# 5V_Buck.net
KiCad netlist of a schematic drawn in Altium Designer
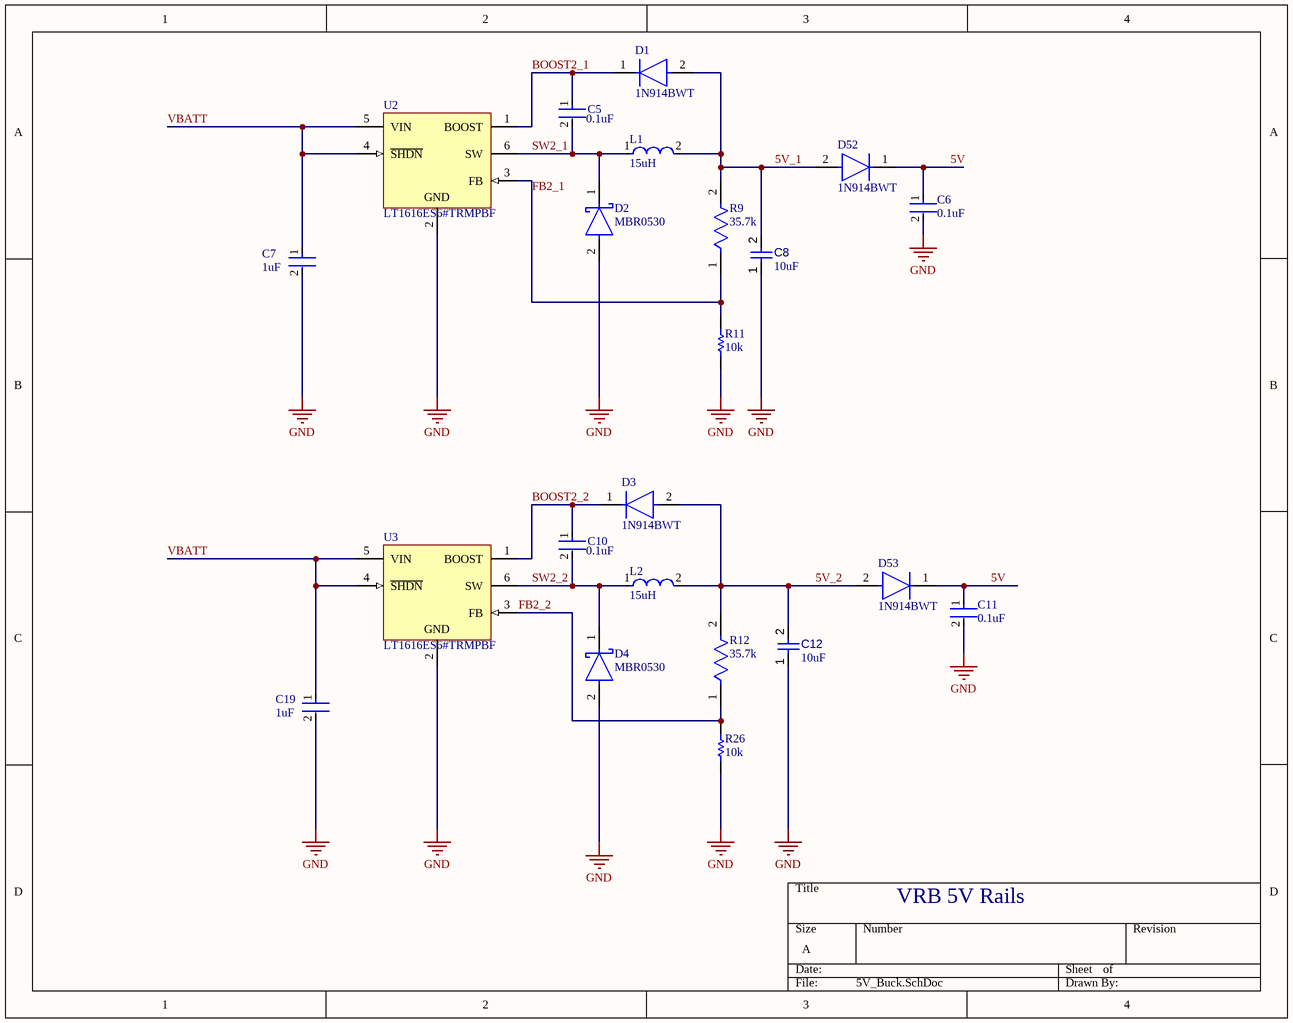
[diagram p0: 5V_Buck.SchDoc]

(export (version "E")
  (design (tool "Eeschema 10.0.6"))
  (components
    (comp (ref "C5")
      (value "0.1uF")
      (footprint "FP-C0603-CJ-MFG")
      (description "CAP CER 0.1UF 50V X7R 0603\r\nC0603X104K5RACTU")
      (fields (field (name "MANUFACTURER PART NUMBER") "C0603X104K5RACTU") (field (name "VOLTAGE") "50V"))
      (libsource (lib "Altium Content Vault") (part "11868f565c42a9108669ba33697ecf6"))
    )
    (comp (ref "C6")
      (value "0.1uF")
      (footprint "FP-C0603-CJ-MFG")
      (description "CAP CER 0.1UF 50V X7R 0603\r\nC0603X104K5RACTU")
      (fields (field (name "MANUFACTURER PART NUMBER") "C0603X104K5RACTU") (field (name "VOLTAGE") "50V"))
      (libsource (lib "Altium Content Vault") (part "11868f565c42a9108669ba33697ecf6"))
    )
    (comp (ref "C7")
      (value "1uF")
      (footprint "FP-CL10-IPC_B")
      (description "Cap Ceramic 1uF 25V X7R ±10% Pad SMD 0603 +125°C T/R\r\nCL10B105KA8NFNC")
      (fields (field (name "TOLERANCE") "10%"))
      (libsource (lib "Altium Content Vault") (part "b4654b650e69147ec39a6b967a45e02"))
    )
    (comp (ref "C8")
      (value "10uF")
      (footprint "CAPC0603(1608)100_L")
      (description "Chip Capacitor, 10µF +/-20%, 10V, 0603, Thickness 1 mm")
      (fields (field (name "TOLERANCE") "10%") (field (name "Comment") "Capacitor 10µF +/-20% 10V 0603"))
      (libsource (lib "University of Georgia") (part "CAP-NP-2"))
    )
    (comp (ref "C10")
      (value "0.1uF")
      (footprint "FP-C0603-CJ-MFG")
      (description "CAP CER 0.1UF 50V X7R 0603\r\nC0603X104K5RACTU")
      (fields (field (name "MANUFACTURER PART NUMBER") "C0603X104K5RACTU") (field (name "VOLTAGE") "50V"))
      (libsource (lib "Altium Content Vault") (part "11868f565c42a9108669ba33697ecf6"))
    )
    (comp (ref "C11")
      (value "0.1uF")
      (footprint "FP-C0603-CJ-MFG")
      (description "CAP CER 0.1UF 50V X7R 0603\r\nC0603X104K5RACTU")
      (fields (field (name "MANUFACTURER PART NUMBER") "C0603X104K5RACTU") (field (name "VOLTAGE") "50V"))
      (libsource (lib "Altium Content Vault") (part "11868f565c42a9108669ba33697ecf6"))
    )
    (comp (ref "C12")
      (value "10uF")
      (footprint "CAPC0603(1608)100_L")
      (description "Chip Capacitor, 10µF +/-20%, 10V, 0603, Thickness 1 mm")
      (fields (field (name "TOLERANCE") "10%") (field (name "Comment") "Capacitor 10µF +/-20% 10V 0603"))
      (libsource (lib "University of Georgia") (part "CAP-NP-2"))
    )
    (comp (ref "C19")
      (value "1uF")
      (footprint "FP-CL10-IPC_B")
      (description "Cap Ceramic 1uF 25V X7R ±10% Pad SMD 0603 +125°C T/R\r\nCL10B105KA8NFNC")
      (fields (field (name "TOLERANCE") "10%"))
      (libsource (lib "Altium Content Vault") (part "b4654b650e69147ec39a6b967a45e02"))
    )
    (comp (ref "D1")
      (value "1N914BWT")
      (footprint "FP-502-01-MFG")
      (description "DIODE GEN PURP 75V 200MA SOD523F")
      (fields
        (field (name "OCTOPART") "https://octopart.com/1n914bwt-on+semiconductor-84323166")
        (field (name "MANUFACTURER") "ON Semiconductor")
      )
      (libsource (lib "Altium Content Vault") (part "d7152d700b627762746794eb795d46e"))
    )
    (comp (ref "D2")
      (value "MBR0530")
      (footprint "FP-425-04-MFG")
      (description "DIODE SCHOTTKY 30V 500MA SOD123")
      (libsource (lib "Altium Content Vault") (part "1d6ec82d83fb6aee721767c19dac4b9"))
    )
    (comp (ref "D3")
      (value "1N914BWT")
      (footprint "FP-502-01-MFG")
      (description "DIODE GEN PURP 75V 200MA SOD523F")
      (fields
        (field (name "OCTOPART") "https://octopart.com/1n914bwt-on+semiconductor-84323166")
        (field (name "MANUFACTURER") "ON Semiconductor")
      )
      (libsource (lib "Altium Content Vault") (part "d7152d700b627762746794eb795d46e"))
    )
    (comp (ref "D4")
      (value "MBR0530")
      (footprint "FP-425-04-MFG")
      (description "DIODE SCHOTTKY 30V 500MA SOD123")
      (libsource (lib "Altium Content Vault") (part "1d6ec82d83fb6aee721767c19dac4b9"))
    )
    (comp (ref "D52")
      (value "1N914BWT")
      (footprint "FP-502-01-MFG")
      (description "DIODE GEN PURP 75V 200MA SOD523F")
      (fields
        (field (name "OCTOPART") "https://octopart.com/1n914bwt-on+semiconductor-84323166")
        (field (name "MANUFACTURER") "ON Semiconductor")
      )
      (libsource (lib "Altium Content Vault") (part "d7152d700b627762746794eb795d46e"))
    )
    (comp (ref "D53")
      (value "1N914BWT")
      (footprint "FP-502-01-MFG")
      (description "DIODE GEN PURP 75V 200MA SOD523F")
      (fields
        (field (name "OCTOPART") "https://octopart.com/1n914bwt-on+semiconductor-84323166")
        (field (name "MANUFACTURER") "ON Semiconductor")
      )
      (libsource (lib "Altium Content Vault") (part "d7152d700b627762746794eb795d46e"))
    )
    (comp (ref "L1")
      (value "15uH")
      (footprint "FP-LQH43CN_03-MFG")
      (description "Wire Wound Ferrite Inductor for General Circuits 15μH ±10% 0.73Ω 360mA 1812")
      (fields (field (name "TOLERANCE") "10%"))
      (libsource (lib "Altium Content Vault") (part "725321dda6339637d4d059423bc1c3c"))
    )
    (comp (ref "L2")
      (value "15uH")
      (footprint "FP-LQH43CN_03-MFG")
      (description "Wire Wound Ferrite Inductor for General Circuits 15μH ±10% 0.73Ω 360mA 1812")
      (fields (field (name "TOLERANCE") "10%"))
      (libsource (lib "Altium Content Vault") (part "725321dda6339637d4d059423bc1c3c"))
    )
    (comp (ref "R9")
      (value "35.7k")
      (footprint "FP-CRCW0603-e3-IPC_C")
      (description "RES Thick Film, 35.7kΩ, 1%, 0.1W, 100ppm/°C, 0603")
      (fields (field (name "TOLERANCE") "1%"))
      (libsource (lib "Altium Content Vault") (part "1029c3af85768c4190bb7ad29bc67b5"))
    )
    (comp (ref "R11")
      (value "10k")
      (footprint "RESC1609X50X30NL8T20")
      (fields (field (name "MANUFACTURER") "Vishay Semiconductor"))
      (libsource (lib "Altium Content Vault") (part "RES-2"))
    )
    (comp (ref "R12")
      (value "35.7k")
      (footprint "FP-CRCW0603-e3-IPC_C")
      (description "RES Thick Film, 35.7kΩ, 1%, 0.1W, 100ppm/°C, 0603")
      (fields (field (name "TOLERANCE") "1%"))
      (libsource (lib "Altium Content Vault") (part "1029c3af85768c4190bb7ad29bc67b5"))
    )
    (comp (ref "R26")
      (value "10k")
      (footprint "RESC1609X50X30NL8T20")
      (fields (field (name "MANUFACTURER") "Vishay Semiconductor"))
      (libsource (lib "Altium Content Vault") (part "RES-2"))
    )
    (comp (ref "U2")
      (value "LT1616ES6#TRMPBF")
      (footprint "LT-S6-6-SOT-23_M")
      (fields (field (name "MANUFACTURER") "Linear Technology"))
      (libsource (lib "Altium Content Vault") (part "LT-LT1616_1933_1934_1934-1"))
    )
    (comp (ref "U3")
      (value "LT1616ES6#TRMPBF")
      (footprint "LT-S6-6-SOT-23_M")
      (fields (field (name "MANUFACTURER") "Linear Technology"))
      (libsource (lib "Altium Content Vault") (part "LT-LT1616_1933_1934_1934-1"))
    )
  )
  (nets
    (net (code "1") (name "/5V") (class "Default")
      (node (ref "C11") (pin "1") (pinfunction "1_1") (pintype "passive"))
      (node (ref "C6") (pin "1") (pinfunction "1_1") (pintype "passive"))
      (node (ref "D52") (pin "1") (pinfunction "C_1") (pintype "passive"))
      (node (ref "D53") (pin "1") (pinfunction "C_1") (pintype "passive"))
    )
    (net (code "2") (name "/5V_1") (class "Default")
      (node (ref "C8") (pin "2") (pinfunction "2_2") (pintype "passive"))
      (node (ref "D1") (pin "2") (pinfunction "A_2") (pintype "passive"))
      (node (ref "D52") (pin "2") (pinfunction "A_2") (pintype "passive"))
      (node (ref "L1") (pin "2") (pinfunction "2_2") (pintype "passive"))
      (node (ref "R9") (pin "2") (pinfunction "2_2") (pintype "passive"))
    )
    (net (code "3") (name "/5V_2") (class "Default")
      (node (ref "C12") (pin "2") (pinfunction "2_2") (pintype "passive"))
      (node (ref "D3") (pin "2") (pinfunction "A_2") (pintype "passive"))
      (node (ref "D53") (pin "2") (pinfunction "A_2") (pintype "passive"))
      (node (ref "L2") (pin "2") (pinfunction "2_2") (pintype "passive"))
      (node (ref "R12") (pin "2") (pinfunction "2_2") (pintype "passive"))
    )
    (net (code "4") (name "/BOOST2_1") (class "Default")
      (node (ref "C5") (pin "1") (pinfunction "1_1") (pintype "passive"))
      (node (ref "D1") (pin "1") (pinfunction "C_1") (pintype "passive"))
      (node (ref "U2") (pin "1") (pinfunction "BOOST_1") (pintype "passive"))
    )
    (net (code "5") (name "/BOOST2_2") (class "Default")
      (node (ref "C10") (pin "1") (pinfunction "1_1") (pintype "passive"))
      (node (ref "D3") (pin "1") (pinfunction "C_1") (pintype "passive"))
      (node (ref "U3") (pin "1") (pinfunction "BOOST_1") (pintype "passive"))
    )
    (net (code "6") (name "/FB2_1") (class "Default")
      (node (ref "R11") (pin "2") (pinfunction "2_2") (pintype "passive"))
      (node (ref "R9") (pin "1") (pinfunction "1_1") (pintype "passive"))
      (node (ref "U2") (pin "3") (pinfunction "FB_3") (pintype "input"))
    )
    (net (code "7") (name "/FB2_2") (class "Default")
      (node (ref "R12") (pin "1") (pinfunction "1_1") (pintype "passive"))
      (node (ref "R26") (pin "2") (pinfunction "2_2") (pintype "passive"))
      (node (ref "U3") (pin "3") (pinfunction "FB_3") (pintype "input"))
    )
    (net (code "8") (name "/SW2_1") (class "Default")
      (node (ref "C5") (pin "2") (pinfunction "2_2") (pintype "passive"))
      (node (ref "D2") (pin "1") (pinfunction "C_1") (pintype "passive"))
      (node (ref "L1") (pin "1") (pinfunction "1_1") (pintype "passive"))
      (node (ref "U2") (pin "6") (pinfunction "SW_6") (pintype "power_in"))
    )
    (net (code "9") (name "/SW2_2") (class "Default")
      (node (ref "C10") (pin "2") (pinfunction "2_2") (pintype "passive"))
      (node (ref "D4") (pin "1") (pinfunction "C_1") (pintype "passive"))
      (node (ref "L2") (pin "1") (pinfunction "1_1") (pintype "passive"))
      (node (ref "U3") (pin "6") (pinfunction "SW_6") (pintype "power_in"))
    )
    (net (code "10") (name "/VBATT") (class "Default")
      (node (ref "C19") (pin "1") (pinfunction "1_1") (pintype "passive"))
      (node (ref "C7") (pin "1") (pinfunction "1_1") (pintype "passive"))
      (node (ref "U2") (pin "4") (pinfunction "~{SHDN}_4") (pintype "input"))
      (node (ref "U2") (pin "5") (pinfunction "VIN_5") (pintype "power_in"))
      (node (ref "U3") (pin "4") (pinfunction "~{SHDN}_4") (pintype "input"))
      (node (ref "U3") (pin "5") (pinfunction "VIN_5") (pintype "power_in"))
    )
    (net (code "11") (name "GND") (class "Default")
      (node (ref "C11") (pin "2") (pinfunction "2_2") (pintype "passive"))
      (node (ref "C12") (pin "1") (pinfunction "1_1") (pintype "passive"))
      (node (ref "C19") (pin "2") (pinfunction "2_2") (pintype "passive"))
      (node (ref "C6") (pin "2") (pinfunction "2_2") (pintype "passive"))
      (node (ref "C7") (pin "2") (pinfunction "2_2") (pintype "passive"))
      (node (ref "C8") (pin "1") (pinfunction "1_1") (pintype "passive"))
      (node (ref "D2") (pin "2") (pinfunction "A_2") (pintype "passive"))
      (node (ref "D4") (pin "2") (pinfunction "A_2") (pintype "passive"))
      (node (ref "R11") (pin "1") (pinfunction "1_1") (pintype "passive"))
      (node (ref "R26") (pin "1") (pinfunction "1_1") (pintype "passive"))
      (node (ref "U2") (pin "2") (pinfunction "GND_2") (pintype "power_in"))
      (node (ref "U3") (pin "2") (pinfunction "GND_2") (pintype "power_in"))
    )
  )
)
